# BSPD.net
KiCad netlist of a schematic drawn in EAGLE
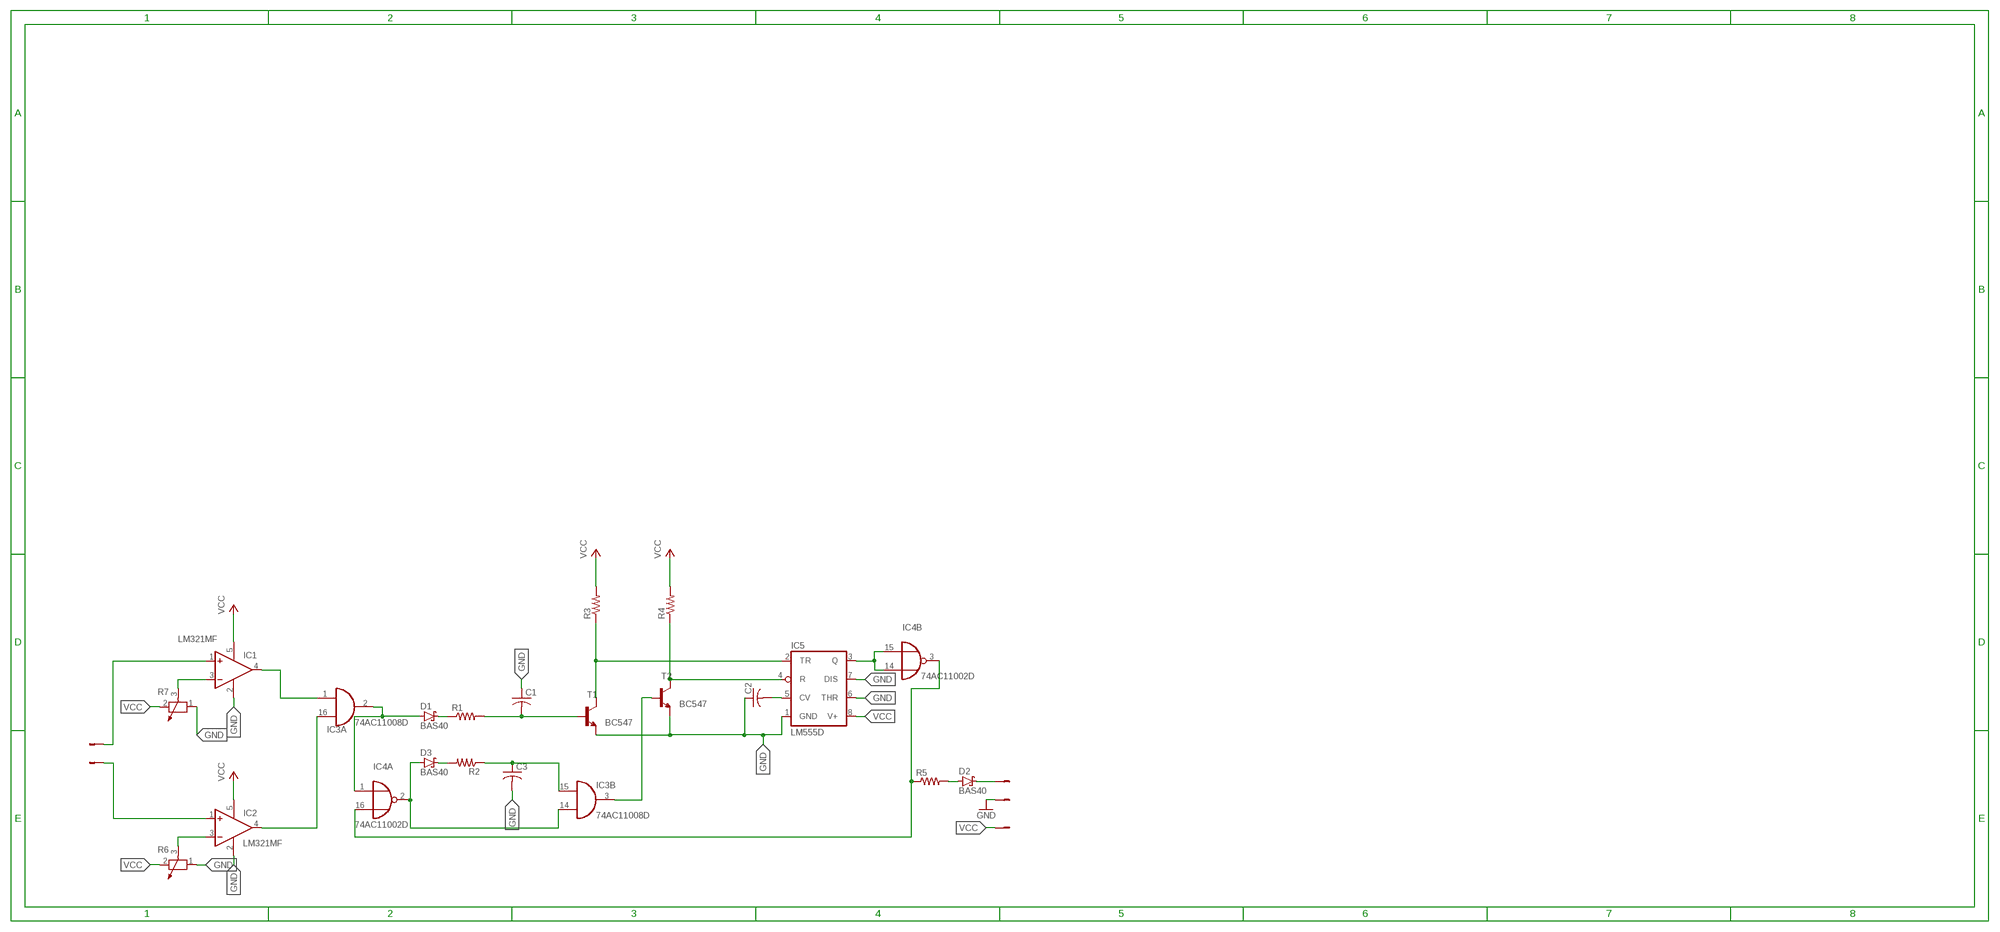
[diagram p0: schematic, sheet 1]

(export (version "E")
  (design (tool "Eeschema 10.0.6"))
  (components
    (comp (ref "C1")
      (value "C-USC0402")
      (footprint "eagle-import:C0402")
      (libsource (lib "eagle-import") (part "C-USC0402"))
    )
    (comp (ref "C2")
      (value "C-USC0402")
      (footprint "eagle-import:C0402")
      (libsource (lib "eagle-import") (part "C-USC0402"))
    )
    (comp (ref "C3")
      (value "C-USC0402")
      (footprint "eagle-import:C0402")
      (libsource (lib "eagle-import") (part "C-USC0402"))
    )
    (comp (ref "D1")
      (value "BAS40")
      (footprint "eagle-import:SOT23")
      (libsource (lib "eagle-import") (part "BAS40"))
    )
    (comp (ref "D2")
      (value "BAS40")
      (footprint "eagle-import:SOT23")
      (libsource (lib "eagle-import") (part "BAS40"))
    )
    (comp (ref "D3")
      (value "BAS40")
      (footprint "eagle-import:SOT23")
      (libsource (lib "eagle-import") (part "BAS40"))
    )
    (comp (ref "IC1")
      (value "LM321MF")
      (footprint "eagle-import:SOT23-5")
      (libsource (lib "eagle-import") (part "LM321?MF"))
    )
    (comp (ref "IC2")
      (value "LM321MF")
      (footprint "eagle-import:SOT23-5")
      (libsource (lib "eagle-import") (part "LM321?MF"))
    )
    (comp (ref "IC3")
      (value "74AC11008D")
      (footprint "eagle-import:SO16")
      (libsource (lib "eagle-import") (part "74AC11008D"))
    )
    (comp (ref "IC4")
      (value "74AC11002D")
      (footprint "eagle-import:SO16")
      (libsource (lib "eagle-import") (part "74AC11002D"))
    )
    (comp (ref "IC5")
      (value "LM555D")
      (footprint "eagle-import:SO08")
      (libsource (lib "eagle-import") (part "555DLM"))
    )
    (comp (ref "R1")
      (value "R-US_M1406")
      (footprint "eagle-import:M1406")
      (libsource (lib "eagle-import") (part "R-US_M1406"))
    )
    (comp (ref "R2")
      (value "R-US_M1406")
      (footprint "eagle-import:M1406")
      (libsource (lib "eagle-import") (part "R-US_M1406"))
    )
    (comp (ref "R3")
      (value "R-US_M1406")
      (footprint "eagle-import:M1406")
      (libsource (lib "eagle-import") (part "R-US_M1406"))
    )
    (comp (ref "R4")
      (value "R-US_M1406")
      (footprint "eagle-import:M1406")
      (libsource (lib "eagle-import") (part "R-US_M1406"))
    )
    (comp (ref "R5")
      (value "R-US_M1406")
      (footprint "eagle-import:M1406")
      (libsource (lib "eagle-import") (part "R-US_M1406"))
    )
    (comp (ref "R6")
      (value "POTENTIOMETER_PT-10")
      (footprint "eagle-import:PT-10")
      (libsource (lib "eagle-import") (part "POTENTIOMETER_PT-10"))
    )
    (comp (ref "R7")
      (value "POTENTIOMETER_PT-10")
      (footprint "eagle-import:PT-10")
      (libsource (lib "eagle-import") (part "POTENTIOMETER_PT-10"))
    )
    (comp (ref "T1")
      (value "BC547")
      (footprint "eagle-import:TO92")
      (libsource (lib "eagle-import") (part "BC547"))
    )
    (comp (ref "T2")
      (value "BC547")
      (footprint "eagle-import:TO92")
      (libsource (lib "eagle-import") (part "BC547"))
    )
    (comp (ref "X1")
      (value "22-23-2021")
      (footprint "eagle-import:22-23-2021")
      (fields (field (name "MF") "MOLEX"))
      (libsource (lib "eagle-import") (part "22-23-2021"))
    )
    (comp (ref "X2")
      (value "22-23-2021")
      (footprint "eagle-import:22-23-2021")
      (fields (field (name "MF") "MOLEX"))
      (libsource (lib "eagle-import") (part "22-23-2021"))
    )
    (comp (ref "X3")
      (value "22-23-2021")
      (footprint "eagle-import:22-23-2021")
      (fields (field (name "MF") "MOLEX"))
      (libsource (lib "eagle-import") (part "22-23-2021"))
    )
  )
  (nets
    (net (code "1") (name "GND") (class "Default")
      (node (ref "C1") (pin "1") (pinfunction "1_1") (pintype "passive"))
      (node (ref "C2") (pin "1") (pinfunction "1_1") (pintype "passive"))
      (node (ref "C3") (pin "2") (pinfunction "2_2") (pintype "passive"))
      (node (ref "IC1") (pin "2") (pinfunction "V-_2") (pintype "power_in"))
      (node (ref "IC2") (pin "2") (pinfunction "V-_2") (pintype "power_in"))
      (node (ref "IC5") (pin "1") (pinfunction "GND_1") (pintype "power_in"))
      (node (ref "IC5") (pin "6") (pinfunction "THR_6") (pintype "input"))
      (node (ref "IC5") (pin "7") (pinfunction "DIS_7") (pintype "input"))
      (node (ref "R6") (pin "1") (pinfunction "1_1") (pintype "passive"))
      (node (ref "R7") (pin "1") (pinfunction "1_1") (pintype "passive"))
      (node (ref "T1") (pin "1") (pinfunction "E_1") (pintype "passive"))
      (node (ref "T2") (pin "1") (pinfunction "E_1") (pintype "passive"))
      (node (ref "X2") (pin "1") (pinfunction "S_1") (pintype "passive"))
    )
    (net (code "2") (name "Net-(D1-A)") (class "Default")
      (node (ref "D1") (pin "1") (pinfunction "A_1") (pintype "passive"))
      (node (ref "IC3") (pin "2") (pinfunction "O_2") (pintype "output"))
      (node (ref "IC4") (pin "1") (pinfunction "I0_1") (pintype "input"))
    )
    (net (code "3") (name "Net-(D1-C)") (class "Default")
      (node (ref "D1") (pin "3") (pinfunction "C_3") (pintype "passive"))
      (node (ref "R1") (pin "1") (pinfunction "1_1") (pintype "passive"))
    )
    (net (code "4") (name "Net-(D2-A)") (class "Default")
      (node (ref "D2") (pin "1") (pinfunction "A_1") (pintype "passive"))
      (node (ref "R5") (pin "2") (pinfunction "2_2") (pintype "passive"))
    )
    (net (code "5") (name "Net-(D2-C)") (class "Default")
      (node (ref "D2") (pin "3") (pinfunction "C_3") (pintype "passive"))
      (node (ref "X2") (pin "2") (pinfunction "S_2") (pintype "passive"))
    )
    (net (code "6") (name "Net-(D3-A)") (class "Default")
      (node (ref "D3") (pin "1") (pinfunction "A_1") (pintype "passive"))
      (node (ref "IC3") (pin "14") (pinfunction "I1_14") (pintype "input"))
      (node (ref "IC4") (pin "2") (pinfunction "O_2") (pintype "output"))
    )
    (net (code "7") (name "Net-(D3-C)") (class "Default")
      (node (ref "D3") (pin "3") (pinfunction "C_3") (pintype "passive"))
      (node (ref "R2") (pin "2") (pinfunction "2_2") (pintype "passive"))
    )
    (net (code "8") (name "Net-(IC1-+IN)") (class "Default")
      (node (ref "IC1") (pin "1") (pinfunction "+IN_1") (pintype "input"))
      (node (ref "X1") (pin "1") (pinfunction "S_1") (pintype "passive"))
    )
    (net (code "9") (name "Net-(IC1--IN)") (class "Default")
      (node (ref "IC1") (pin "3") (pinfunction "-IN_3") (pintype "input"))
      (node (ref "R7") (pin "3") (pinfunction "3_3") (pintype "passive"))
    )
    (net (code "10") (name "Net-(IC1-OUT)") (class "Default")
      (node (ref "IC1") (pin "4") (pinfunction "OUT_4") (pintype "output"))
      (node (ref "IC3") (pin "1") (pinfunction "I0_1") (pintype "input"))
    )
    (net (code "11") (name "Net-(IC2-+IN)") (class "Default")
      (node (ref "IC2") (pin "1") (pinfunction "+IN_1") (pintype "input"))
      (node (ref "X1") (pin "2") (pinfunction "S_2") (pintype "passive"))
    )
    (net (code "12") (name "Net-(IC2--IN)") (class "Default")
      (node (ref "IC2") (pin "3") (pinfunction "-IN_3") (pintype "input"))
      (node (ref "R6") (pin "3") (pinfunction "3_3") (pintype "passive"))
    )
    (net (code "13") (name "Net-(IC2-OUT)") (class "Default")
      (node (ref "IC2") (pin "4") (pinfunction "OUT_4") (pintype "output"))
      (node (ref "IC3") (pin "16") (pinfunction "I1_16") (pintype "input"))
    )
    (net (code "14") (name "Net-(IC3B-I0)") (class "Default")
      (node (ref "C3") (pin "1") (pinfunction "1_1") (pintype "passive"))
      (node (ref "IC3") (pin "15") (pinfunction "I0_15") (pintype "input"))
      (node (ref "R2") (pin "1") (pinfunction "1_1") (pintype "passive"))
    )
    (net (code "15") (name "Net-(IC3B-O)") (class "Default")
      (node (ref "IC3") (pin "3") (pinfunction "O_3") (pintype "output"))
      (node (ref "T2") (pin "2") (pinfunction "B_2") (pintype "passive"))
    )
    (net (code "16") (name "Net-(IC4A-I1)") (class "Default")
      (node (ref "IC4") (pin "16") (pinfunction "I1_16") (pintype "input"))
      (node (ref "IC4") (pin "3") (pinfunction "O_3") (pintype "output"))
      (node (ref "R5") (pin "1") (pinfunction "1_1") (pintype "passive"))
    )
    (net (code "17") (name "Net-(IC4B-I0)") (class "Default")
      (node (ref "IC4") (pin "14") (pinfunction "I1_14") (pintype "input"))
      (node (ref "IC4") (pin "15") (pinfunction "I0_15") (pintype "input"))
      (node (ref "IC5") (pin "3") (pinfunction "Q_3") (pintype "output"))
    )
    (net (code "18") (name "Net-(IC5-CV)") (class "Default")
      (node (ref "C2") (pin "2") (pinfunction "2_2") (pintype "passive"))
      (node (ref "IC5") (pin "5") (pinfunction "CV_5") (pintype "input"))
    )
    (net (code "19") (name "Net-(IC5-R)") (class "Default")
      (node (ref "IC5") (pin "4") (pinfunction "R_4") (pintype "input"))
      (node (ref "R4") (pin "1") (pinfunction "1_1") (pintype "passive"))
      (node (ref "T2") (pin "3") (pinfunction "C_3") (pintype "passive"))
    )
    (net (code "20") (name "Net-(IC5-TR)") (class "Default")
      (node (ref "IC5") (pin "2") (pinfunction "TR_2") (pintype "input"))
      (node (ref "R3") (pin "1") (pinfunction "1_1") (pintype "passive"))
      (node (ref "T1") (pin "3") (pinfunction "C_3") (pintype "passive"))
    )
    (net (code "21") (name "Net-(T1-B)") (class "Default")
      (node (ref "C1") (pin "2") (pinfunction "2_2") (pintype "passive"))
      (node (ref "R1") (pin "2") (pinfunction "2_2") (pintype "passive"))
      (node (ref "T1") (pin "2") (pinfunction "B_2") (pintype "passive"))
    )
    (net (code "22") (name "VCC") (class "Default")
      (node (ref "IC1") (pin "5") (pinfunction "V+_5") (pintype "power_in"))
      (node (ref "IC2") (pin "5") (pinfunction "V+_5") (pintype "power_in"))
      (node (ref "IC5") (pin "8") (pinfunction "V+_8") (pintype "power_in"))
      (node (ref "R3") (pin "2") (pinfunction "2_2") (pintype "passive"))
      (node (ref "R4") (pin "2") (pinfunction "2_2") (pintype "passive"))
      (node (ref "R6") (pin "2") (pinfunction "2_2") (pintype "passive"))
      (node (ref "R7") (pin "2") (pinfunction "2_2") (pintype "passive"))
      (node (ref "X3") (pin "1") (pinfunction "S_1") (pintype "passive"))
    )
  )
)
